# LIN_SCH.net
KiCad netlist of a schematic drawn in Altium Designer
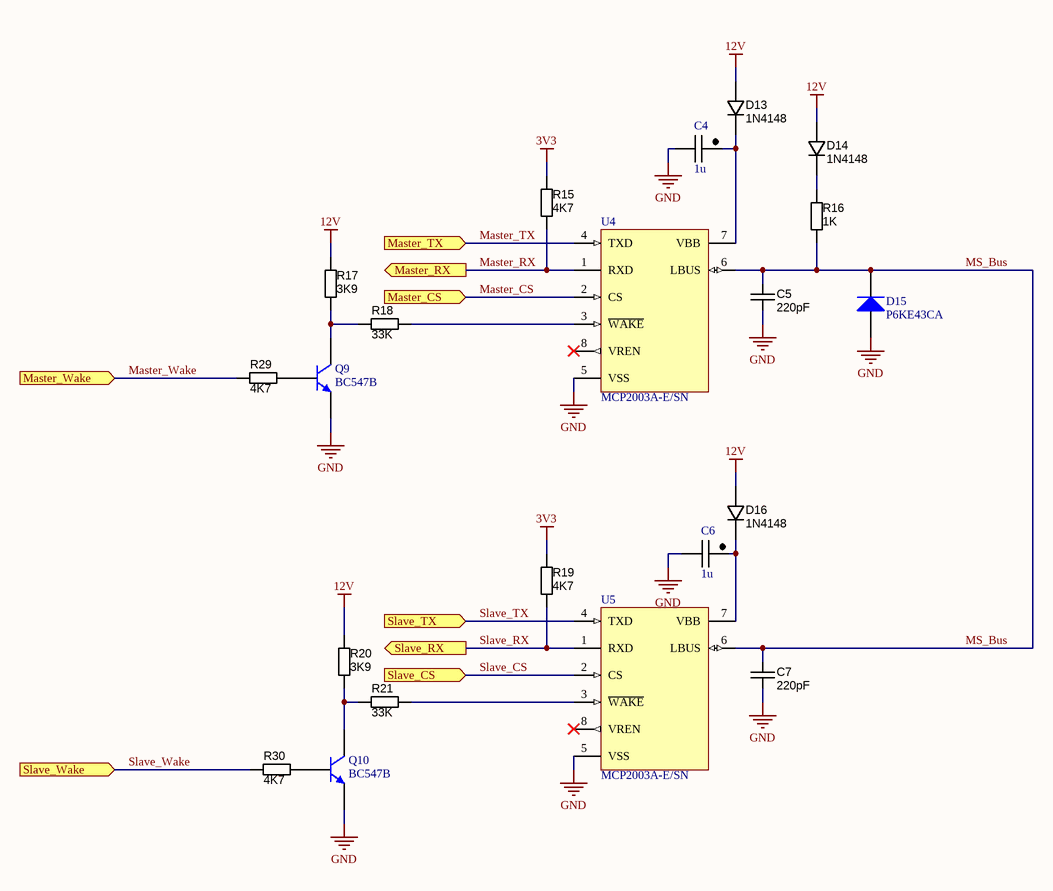
[diagram p0: LIN_SCH.SchDoc]

(export (version "E")
  (design (tool "Eeschema 10.0.6"))
  (components
    (comp (ref "C4")
      (value "1u")
      (footprint "CAP_Elec_5x5.7")
      (libsource (lib "Ampli_Lib_Sch") (part "CAP_Elec_4x4"))
    )
    (comp (ref "C5")
      (value "220pF")
      (footprint "CAPC1608X90N")
      (description "Capacitor SMD Cer 220pF 10% 50V X7R 0603")
      (fields (field (name "TOLERANCE") "±10%"))
      (libsource (lib "PBL - Capacitors") (part "CAPC_47n_0603_X7R_50V_10%"))
    )
    (comp (ref "C6")
      (value "1u")
      (footprint "CAP_Elec_5x5.7")
      (libsource (lib "Ampli_Lib_Sch") (part "CAP_Elec_4x4"))
    )
    (comp (ref "C7")
      (value "220pF")
      (footprint "CAPC1608X90N")
      (description "Capacitor SMD Cer 220pF 10% 50V X7R 0603")
      (fields (field (name "TOLERANCE") "±10%"))
      (libsource (lib "PBL - Capacitors") (part "CAPC_47n_0603_X7R_50V_10%"))
    )
    (comp (ref "D13")
      (value "1N4148")
      (footprint "SOD523F")
      (description "Diode 1N4148 SMD SOD-523F")
      (libsource (lib "PBL - Diodes") (part "DIODE_1N4148_200mA_SOD523F"))
    )
    (comp (ref "D14")
      (value "1N4148")
      (footprint "SOD523F")
      (description "Diode 1N4148 SMD SOD-523F")
      (libsource (lib "PBL - Diodes") (part "DIODE_1N4148_200mA_SOD523F"))
    )
    (comp (ref "D15")
      (value "P6KE43CA")
      (footprint "DO-41")
      (description "1 Amp General Purpose Rectifier Do-41")
      (fields (field (name "PUBLISHER") "Altium Limited"))
      (libsource (lib "Miscellaneous Devices") (part "Diode 1N4007"))
    )
    (comp (ref "D16")
      (value "1N4148")
      (footprint "SOD523F")
      (description "Diode 1N4148 SMD SOD-523F")
      (libsource (lib "PBL - Diodes") (part "DIODE_1N4148_200mA_SOD523F"))
    )
    (comp (ref "Q9")
      (value "BC547B")
      (footprint "TO-92A")
      (description "NPN General Purpose Amplifier")
      (fields (field (name "PUBLISHER") "Altium Limited"))
      (libsource (lib "Miscellaneous Devices") (part "2N3904"))
    )
    (comp (ref "Q10")
      (value "BC547B")
      (footprint "TO-92A")
      (description "NPN General Purpose Amplifier")
      (fields (field (name "PUBLISHER") "Altium Limited"))
      (libsource (lib "Miscellaneous Devices") (part "2N3904"))
    )
    (comp (ref "R15")
      (value "4K7")
      (footprint "RESC1608N_ZERO")
      (description "Resistor SMD 0603 4.7K 5%")
      (fields (field (name "TOLERANCE") "±5%"))
      (libsource (lib "PBL - Resistors") (part "RES_0R_0603"))
    )
    (comp (ref "R16")
      (value "1K")
      (footprint "RESC1608N_ZERO")
      (description "Resistor SMD 0603 1K 5%")
      (fields (field (name "TOLERANCE") "±5%"))
      (libsource (lib "PBL - Resistors") (part "RES_0R_0603"))
    )
    (comp (ref "R17")
      (value "3K9")
      (footprint "RESC1608N_ZERO")
      (description "Resistor SMD 0603 3.9K 5%")
      (fields (field (name "TOLERANCE") "±5%"))
      (libsource (lib "PBL - Resistors") (part "RES_0R_0603"))
    )
    (comp (ref "R18")
      (value "33K")
      (footprint "RESC1608N_ZERO")
      (description "Resistor SMD 0603 33K 5%")
      (fields (field (name "TOLERANCE") "±5%"))
      (libsource (lib "") (part "RES_0R_0603_1"))
    )
    (comp (ref "R19")
      (value "4K7")
      (footprint "RESC1608N_ZERO")
      (description "Resistor SMD 0603 4.7K 5%")
      (fields (field (name "TOLERANCE") "±5%"))
      (libsource (lib "PBL - Resistors") (part "RES_0R_0603"))
    )
    (comp (ref "R20")
      (value "3K9")
      (footprint "RESC1608N_ZERO")
      (description "Resistor SMD 0603 3.9K 5%")
      (fields (field (name "TOLERANCE") "±5%"))
      (libsource (lib "PBL - Resistors") (part "RES_0R_0603"))
    )
    (comp (ref "R21")
      (value "33K")
      (footprint "RESC1608N_ZERO")
      (description "Resistor SMD 0603 33K 5%")
      (fields (field (name "TOLERANCE") "±5%"))
      (libsource (lib "") (part "RES_0R_0603_1"))
    )
    (comp (ref "R29")
      (value "4K7")
      (footprint "RESC1608N_ZERO")
      (description "Resistor SMD 0603 4.7K 5%")
      (fields (field (name "TOLERANCE") "±5%"))
      (libsource (lib "") (part "RES_0R_0603_1"))
    )
    (comp (ref "R30")
      (value "4K7")
      (footprint "RESC1608N_ZERO")
      (description "Resistor SMD 0603 4.7K 5%")
      (fields (field (name "TOLERANCE") "±5%"))
      (libsource (lib "") (part "RES_0R_0603_1"))
    )
    (comp (ref "U4")
      (value "MCP2003A-E/SN")
      (footprint "SOIC-SN8_N")
      (description "LIN J2602 Transceiver, 8-Pin SOIC, Extended Temperature")
      (libsource (lib "Altium Content Vault") (part "COM-TRX-MCP2003-8"))
    )
    (comp (ref "U5")
      (value "MCP2003A-E/SN")
      (footprint "SOIC-SN8_N")
      (description "LIN J2602 Transceiver, 8-Pin SOIC, Extended Temperature")
      (libsource (lib "Altium Content Vault") (part "COM-TRX-MCP2003-8"))
    )
  )
  (nets
    (net (code "1") (name "/MS_Bus") (class "Default")
      (node (ref "C5") (pin "1") (pintype "passive"))
      (node (ref "C7") (pin "1") (pintype "passive"))
      (node (ref "D15") (pin "2") (pinfunction "K_2") (pintype "passive"))
      (node (ref "R16") (pin "2") (pinfunction "2_2") (pintype "passive"))
      (node (ref "U4") (pin "6") (pinfunction "LBUS_6") (pintype "bidirectional"))
      (node (ref "U5") (pin "6") (pinfunction "LBUS_6") (pintype "bidirectional"))
    )
    (net (code "2") (name "/Master_CS") (class "Default")
      (node (ref "U4") (pin "2") (pinfunction "CS_2") (pintype "input"))
    )
    (net (code "3") (name "/Master_RX") (class "Default")
      (node (ref "R15") (pin "2") (pinfunction "2_2") (pintype "passive"))
      (node (ref "U4") (pin "1") (pinfunction "RXD_1") (pintype "open_collector"))
    )
    (net (code "4") (name "/Master_TX") (class "Default")
      (node (ref "U4") (pin "4") (pinfunction "TXD_4") (pintype "input"))
    )
    (net (code "5") (name "/Master_Wake") (class "Default")
      (node (ref "R29") (pin "1") (pinfunction "1_1") (pintype "passive"))
    )
    (net (code "6") (name "/Slave_CS") (class "Default")
      (node (ref "U5") (pin "2") (pinfunction "CS_2") (pintype "input"))
    )
    (net (code "7") (name "/Slave_RX") (class "Default")
      (node (ref "R19") (pin "2") (pinfunction "2_2") (pintype "passive"))
      (node (ref "U5") (pin "1") (pinfunction "RXD_1") (pintype "open_collector"))
    )
    (net (code "8") (name "/Slave_TX") (class "Default")
      (node (ref "U5") (pin "4") (pinfunction "TXD_4") (pintype "input"))
    )
    (net (code "9") (name "/Slave_Wake") (class "Default")
      (node (ref "R30") (pin "1") (pinfunction "1_1") (pintype "passive"))
    )
    (net (code "10") (name "3V3") (class "Default")
      (node (ref "R15") (pin "1") (pinfunction "1_1") (pintype "passive"))
      (node (ref "R19") (pin "1") (pinfunction "1_1") (pintype "passive"))
    )
    (net (code "11") (name "12V") (class "Default")
      (node (ref "D13") (pin "A") (pinfunction "A_A") (pintype "passive"))
      (node (ref "D14") (pin "A") (pinfunction "A_A") (pintype "passive"))
      (node (ref "D16") (pin "A") (pinfunction "A_A") (pintype "passive"))
      (node (ref "R17") (pin "1") (pinfunction "1_1") (pintype "passive"))
      (node (ref "R20") (pin "1") (pinfunction "1_1") (pintype "passive"))
    )
    (net (code "12") (name "GND") (class "Default")
      (node (ref "C4") (pin "2") (pinfunction "2_2") (pintype "passive"))
      (node (ref "C5") (pin "2") (pintype "passive"))
      (node (ref "C6") (pin "2") (pinfunction "2_2") (pintype "passive"))
      (node (ref "C7") (pin "2") (pintype "passive"))
      (node (ref "D15") (pin "1") (pinfunction "A_1") (pintype "passive"))
      (node (ref "Q10") (pin "1") (pinfunction "E_1") (pintype "passive"))
      (node (ref "Q9") (pin "1") (pinfunction "E_1") (pintype "passive"))
      (node (ref "U4") (pin "5") (pinfunction "VSS_5") (pintype "power_in"))
      (node (ref "U5") (pin "5") (pinfunction "VSS_5") (pintype "power_in"))
    )
    (net (code "13") (name "Net-(D14-PadK)") (class "Default")
      (node (ref "D14") (pin "K") (pinfunction "K_K") (pintype "passive"))
      (node (ref "R16") (pin "1") (pinfunction "1_1") (pintype "passive"))
    )
    (net (code "14") (name "Net-(Q9-B)") (class "Default")
      (node (ref "Q9") (pin "2") (pinfunction "B_2") (pintype "passive"))
      (node (ref "R29") (pin "2") (pinfunction "2_2") (pintype "passive"))
    )
    (net (code "15") (name "Net-(Q9-C)") (class "Default")
      (node (ref "Q9") (pin "3") (pinfunction "C_3") (pintype "passive"))
      (node (ref "R17") (pin "2") (pinfunction "2_2") (pintype "passive"))
      (node (ref "R18") (pin "1") (pinfunction "1_1") (pintype "passive"))
    )
    (net (code "16") (name "Net-(Q10-B)") (class "Default")
      (node (ref "Q10") (pin "2") (pinfunction "B_2") (pintype "passive"))
      (node (ref "R30") (pin "2") (pinfunction "2_2") (pintype "passive"))
    )
    (net (code "17") (name "Net-(Q10-C)") (class "Default")
      (node (ref "Q10") (pin "3") (pinfunction "C_3") (pintype "passive"))
      (node (ref "R20") (pin "2") (pinfunction "2_2") (pintype "passive"))
      (node (ref "R21") (pin "1") (pinfunction "1_1") (pintype "passive"))
    )
    (net (code "18") (name "Net-(U4-VBB)") (class "Default")
      (node (ref "C4") (pin "1") (pinfunction "1_1") (pintype "passive"))
      (node (ref "D13") (pin "K") (pinfunction "K_K") (pintype "passive"))
      (node (ref "U4") (pin "7") (pinfunction "VBB_7") (pintype "power_in"))
    )
    (net (code "19") (name "Net-(U4-~{WAKE})") (class "Default")
      (node (ref "R18") (pin "2") (pinfunction "2_2") (pintype "passive"))
      (node (ref "U4") (pin "3") (pinfunction "~{WAKE}_3") (pintype "input"))
    )
    (net (code "20") (name "Net-(U5-VBB)") (class "Default")
      (node (ref "C6") (pin "1") (pinfunction "1_1") (pintype "passive"))
      (node (ref "D16") (pin "K") (pinfunction "K_K") (pintype "passive"))
      (node (ref "U5") (pin "7") (pinfunction "VBB_7") (pintype "power_in"))
    )
    (net (code "21") (name "Net-(U5-~{WAKE})") (class "Default")
      (node (ref "R21") (pin "2") (pinfunction "2_2") (pintype "passive"))
      (node (ref "U5") (pin "3") (pinfunction "~{WAKE}_3") (pintype "input"))
    )
    (net (code "22") (name "unconnected-(U4-VREN-Pad8)") (class "Default")
      (node (ref "U4") (pin "8") (pinfunction "VREN_8") (pintype "output+no_connect"))
    )
    (net (code "23") (name "unconnected-(U5-VREN-Pad8)") (class "Default")
      (node (ref "U5") (pin "8") (pinfunction "VREN_8") (pintype "output+no_connect"))
    )
  )
)
